# 01-USER_IO.net
KiCad netlist of a schematic drawn in Altium Designer
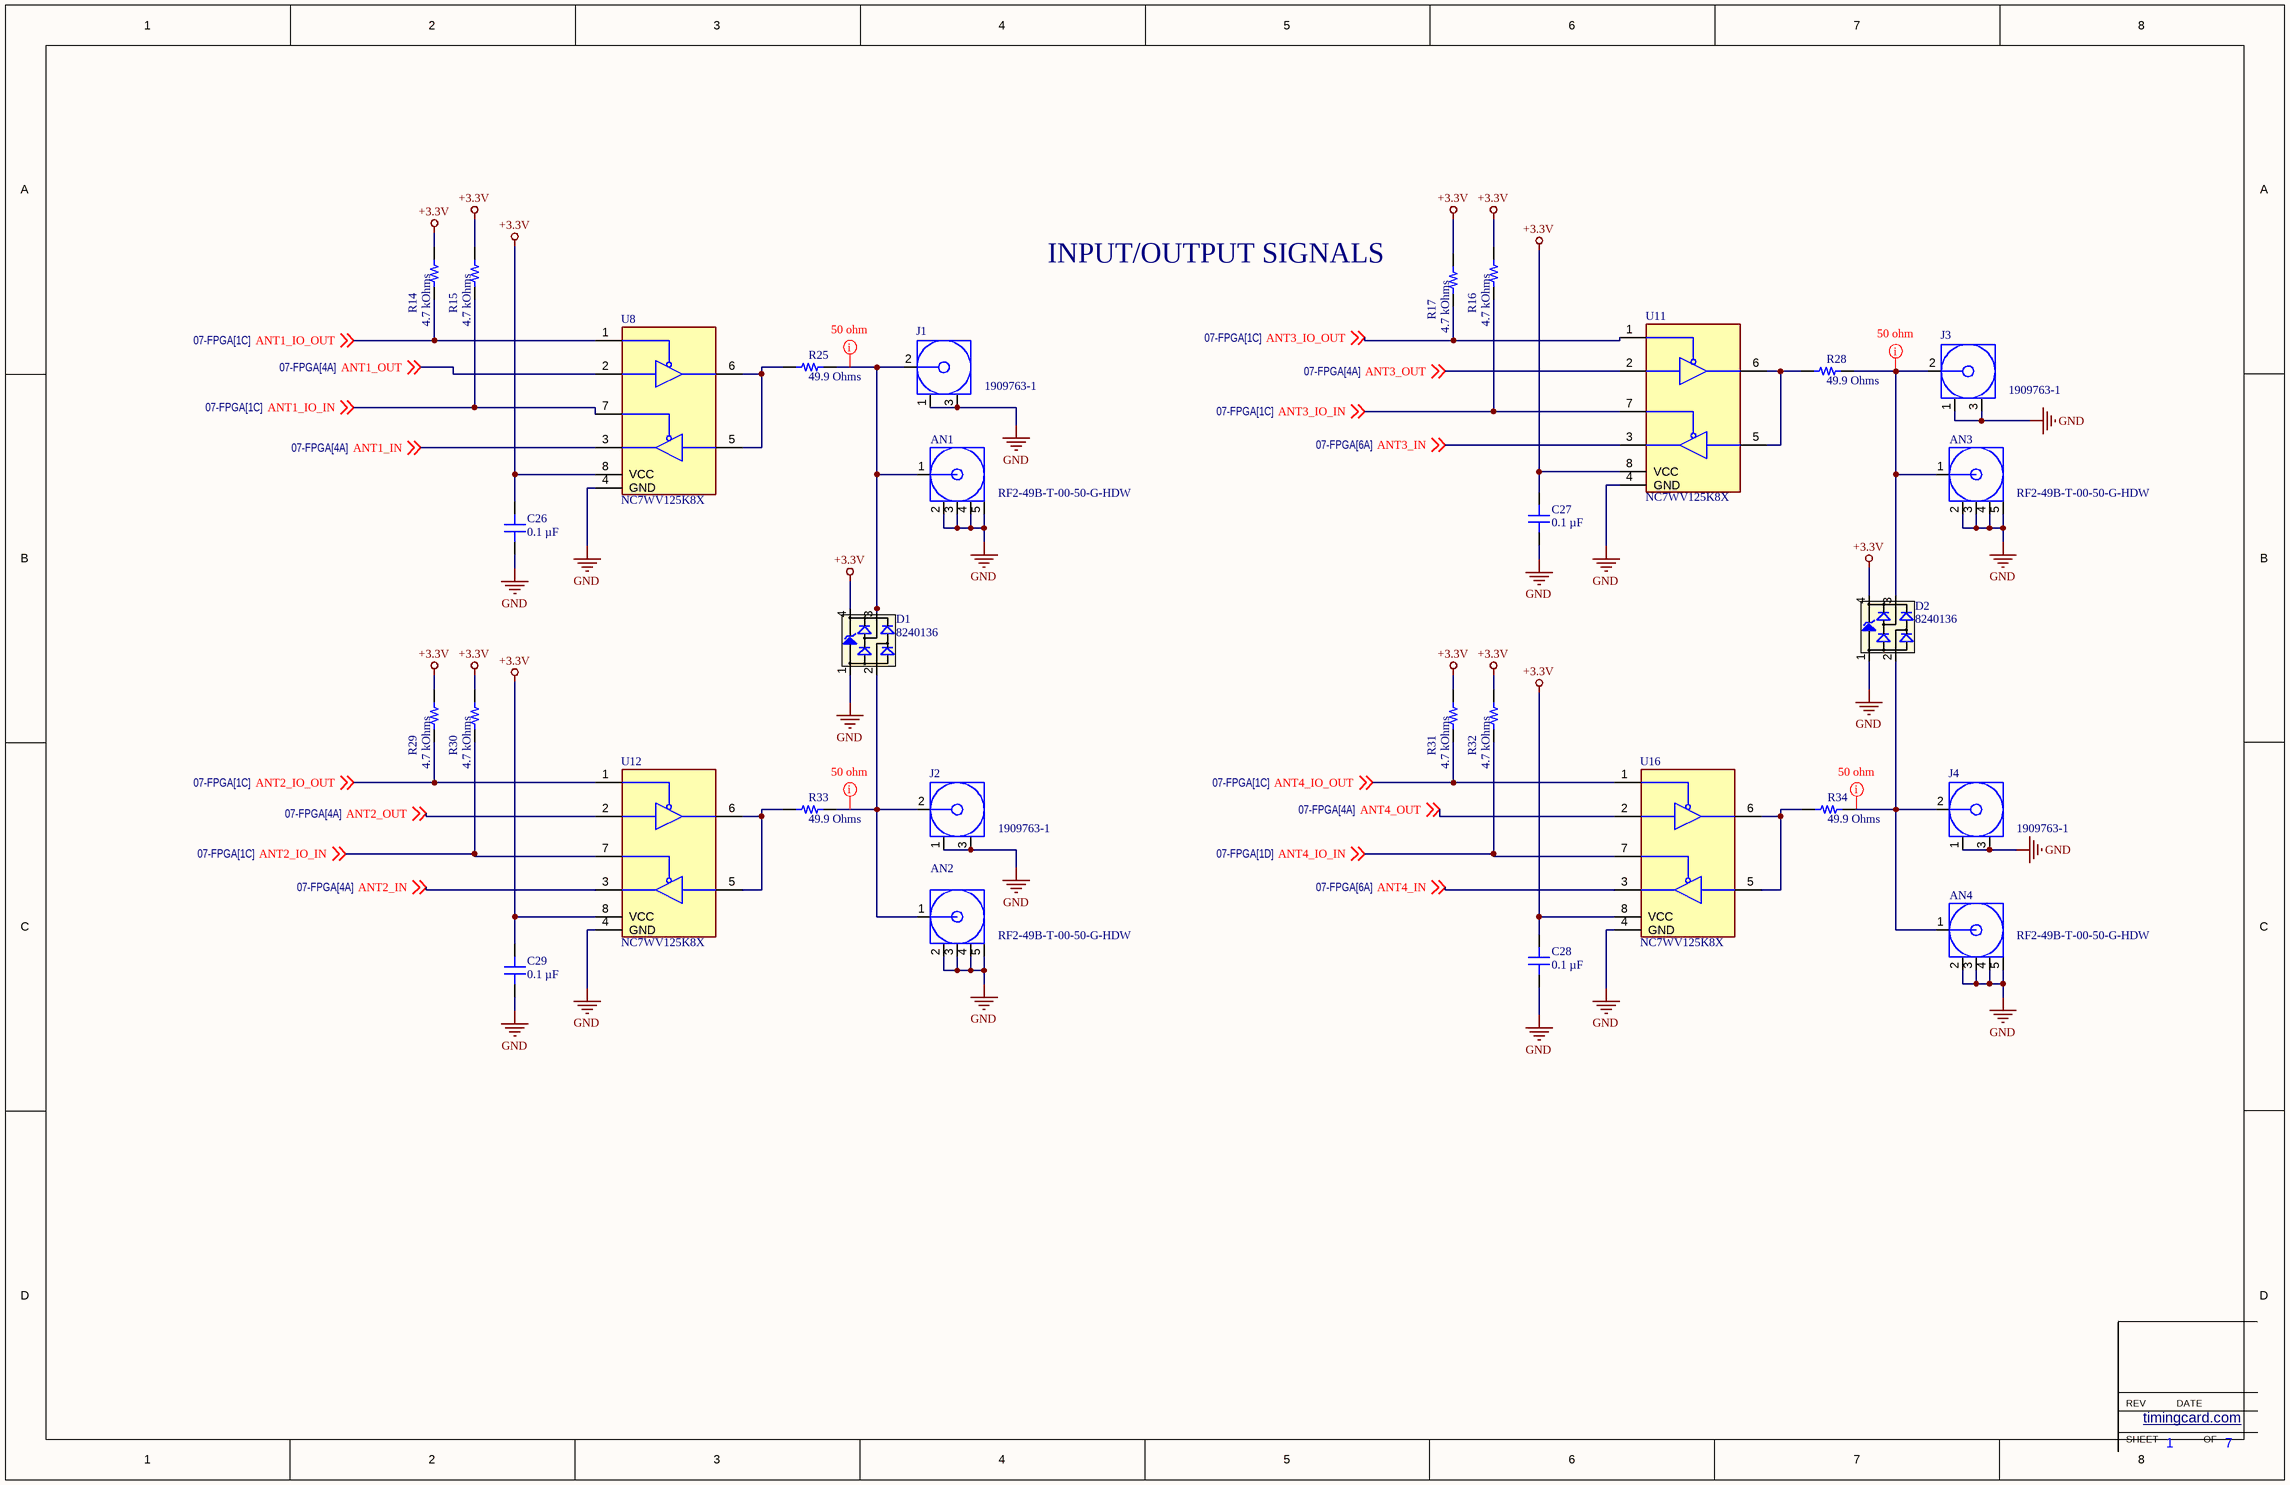
[diagram p0: 01-USER_IO.SchDoc]

(export (version "E")
  (design (tool "Eeschema 10.0.6"))
  (components
    (comp (ref "AN1")
      (value "RF2-49B-T-00-50-G-HDW")
      (footprint "SamacSys:RF249BT0050GHDW")
      (description "Connector")
      (libsource (lib "SamacSys") (part "RF2-49B-T-00-50-G-HDW"))
    )
    (comp (ref "AN2")
      (value "RF2-49B-T-00-50-G-HDW")
      (footprint "SamacSys:RF249BT0050GHDW")
      (description "Connector")
      (libsource (lib "SamacSys") (part "RF2-49B-T-00-50-G-HDW"))
    )
    (comp (ref "AN3")
      (value "RF2-49B-T-00-50-G-HDW")
      (footprint "SamacSys:RF249BT0050GHDW")
      (description "Connector")
      (libsource (lib "SamacSys") (part "RF2-49B-T-00-50-G-HDW"))
    )
    (comp (ref "AN4")
      (value "RF2-49B-T-00-50-G-HDW")
      (footprint "SamacSys:RF249BT0050GHDW")
      (description "Connector")
      (libsource (lib "SamacSys") (part "RF2-49B-T-00-50-G-HDW"))
    )
    (comp (ref "C26")
      (value "0.1 µF")
      (footprint "CAP 0402_1005")
      (description "CAP CER 0.1UF 50V X7R 0402")
      (fields (field (name "TOLERANCE") "±10%") (field (name "PART NUMBER") "CC0402KRX7R9BB104"))
      (libsource (lib "Celestial Altium Library - altium_library") (part "Capacitor"))
    )
    (comp (ref "C27")
      (value "0.1 µF")
      (footprint "CAP 0402_1005")
      (description "CAP CER 0.1UF 50V X7R 0402")
      (fields (field (name "TOLERANCE") "±10%") (field (name "PART NUMBER") "CC0402KRX7R9BB104"))
      (libsource (lib "Celestial Altium Library - altium_library") (part "Capacitor"))
    )
    (comp (ref "C28")
      (value "0.1 µF")
      (footprint "CAP 0402_1005")
      (description "CAP CER 0.1UF 50V X7R 0402")
      (fields (field (name "TOLERANCE") "±10%") (field (name "PART NUMBER") "CC0402KRX7R9BB104"))
      (libsource (lib "Celestial Altium Library - altium_library") (part "Capacitor"))
    )
    (comp (ref "C29")
      (value "0.1 µF")
      (footprint "CAP 0402_1005")
      (description "CAP CER 0.1UF 50V X7R 0402")
      (fields (field (name "TOLERANCE") "±10%") (field (name "PART NUMBER") "CC0402KRX7R9BB104"))
      (libsource (lib "Celestial Altium Library - altium_library") (part "Capacitor"))
    )
    (comp (ref "D1")
      (value "8240136")
      (footprint "SOT143-4L")
      (description "TVS Diode WE-TVS-HS, VRWM=3.3V")
      (fields (field (name "MANUFACTURER") "Wuerth Elektronik"))
      (libsource (lib "Altium Content Vault") (part "WE-TVS-HS-4"))
    )
    (comp (ref "D2")
      (value "8240136")
      (footprint "SOT143-4L")
      (description "TVS Diode WE-TVS-HS, VRWM=3.3V")
      (fields (field (name "MANUFACTURER") "Wuerth Elektronik"))
      (libsource (lib "Altium Content Vault") (part "WE-TVS-HS-4"))
    )
    (comp (ref "J1")
      (value "1909763-1")
      (footprint "TECO-1909763-1_V")
      (description "Ultra Miniature Coaxial Connector Jack, 60 V, 50 Ohm, -40 to 90 degC, RoHS, Tape and Reel")
      (fields (field (name "MANUFACTURER") "TE Connectivity"))
      (libsource (lib "Altium Content Vault") (part "CN-1P-M-RF3"))
    )
    (comp (ref "J2")
      (value "1909763-1")
      (footprint "TECO-1909763-1_V")
      (description "Ultra Miniature Coaxial Connector Jack, 60 V, 50 Ohm, -40 to 90 degC, RoHS, Tape and Reel")
      (fields (field (name "MANUFACTURER") "TE Connectivity"))
      (libsource (lib "Altium Content Vault") (part "CN-1P-M-RF3"))
    )
    (comp (ref "J3")
      (value "1909763-1")
      (footprint "TECO-1909763-1_V")
      (description "Ultra Miniature Coaxial Connector Jack, 60 V, 50 Ohm, -40 to 90 degC, RoHS, Tape and Reel")
      (fields (field (name "MANUFACTURER") "TE Connectivity"))
      (libsource (lib "Altium Content Vault") (part "CN-1P-M-RF3"))
    )
    (comp (ref "J4")
      (value "1909763-1")
      (footprint "TECO-1909763-1_V")
      (description "Ultra Miniature Coaxial Connector Jack, 60 V, 50 Ohm, -40 to 90 degC, RoHS, Tape and Reel")
      (fields (field (name "MANUFACTURER") "TE Connectivity"))
      (libsource (lib "Altium Content Vault") (part "CN-1P-M-RF3"))
    )
    (comp (ref "R14")
      (value "4.7 kOhms")
      (footprint "YAGEO RES 0402_1005")
      (description "RES 4.7K OHM 1% 1/16W 0402")
      (fields (field (name "MANUFACTURER") "Yageo") (field (name "PART NUMBER") "RC0402FR-074K7L"))
      (libsource (lib "Celestial Altium Library - altium_library") (part "Resistor"))
    )
    (comp (ref "R15")
      (value "4.7 kOhms")
      (footprint "YAGEO RES 0402_1005")
      (description "RES 4.7K OHM 1% 1/16W 0402")
      (fields (field (name "MANUFACTURER") "Yageo") (field (name "PART NUMBER") "RC0402FR-074K7L"))
      (libsource (lib "Celestial Altium Library - altium_library") (part "Resistor"))
    )
    (comp (ref "R16")
      (value "4.7 kOhms")
      (footprint "YAGEO RES 0402_1005")
      (description "RES 4.7K OHM 1% 1/16W 0402")
      (fields (field (name "MANUFACTURER") "Yageo") (field (name "PART NUMBER") "RC0402FR-074K7L"))
      (libsource (lib "Celestial Altium Library - altium_library") (part "Resistor"))
    )
    (comp (ref "R17")
      (value "4.7 kOhms")
      (footprint "YAGEO RES 0402_1005")
      (description "RES 4.7K OHM 1% 1/16W 0402")
      (fields (field (name "MANUFACTURER") "Yageo") (field (name "PART NUMBER") "RC0402FR-074K7L"))
      (libsource (lib "Celestial Altium Library - altium_library") (part "Resistor"))
    )
    (comp (ref "R25")
      (value "49.9 Ohms")
      (footprint "YAGEO RES 0402_1005")
      (description "RES 49.9 OHM 1% 1/16W 0402")
      (fields (field (name "PART NUMBER") "RC0402FR-0749R9L") (field (name "MANUFACTURER") "Yageo"))
      (libsource (lib "Celestial Altium Library - altium_library") (part "Resistor"))
    )
    (comp (ref "R28")
      (value "49.9 Ohms")
      (footprint "YAGEO RES 0402_1005")
      (description "RES 49.9 OHM 1% 1/16W 0402")
      (fields (field (name "PART NUMBER") "RC0402FR-0749R9L") (field (name "MANUFACTURER") "Yageo"))
      (libsource (lib "Celestial Altium Library - altium_library") (part "Resistor"))
    )
    (comp (ref "R29")
      (value "4.7 kOhms")
      (footprint "YAGEO RES 0402_1005")
      (description "RES 4.7K OHM 1% 1/16W 0402")
      (fields (field (name "MANUFACTURER") "Yageo") (field (name "PART NUMBER") "RC0402FR-074K7L"))
      (libsource (lib "Celestial Altium Library - altium_library") (part "Resistor"))
    )
    (comp (ref "R30")
      (value "4.7 kOhms")
      (footprint "YAGEO RES 0402_1005")
      (description "RES 4.7K OHM 1% 1/16W 0402")
      (fields (field (name "MANUFACTURER") "Yageo") (field (name "PART NUMBER") "RC0402FR-074K7L"))
      (libsource (lib "Celestial Altium Library - altium_library") (part "Resistor"))
    )
    (comp (ref "R31")
      (value "4.7 kOhms")
      (footprint "YAGEO RES 0402_1005")
      (description "RES 4.7K OHM 1% 1/16W 0402")
      (fields (field (name "MANUFACTURER") "Yageo") (field (name "PART NUMBER") "RC0402FR-074K7L"))
      (libsource (lib "Celestial Altium Library - altium_library") (part "Resistor"))
    )
    (comp (ref "R32")
      (value "4.7 kOhms")
      (footprint "YAGEO RES 0402_1005")
      (description "RES 4.7K OHM 1% 1/16W 0402")
      (fields (field (name "MANUFACTURER") "Yageo") (field (name "PART NUMBER") "RC0402FR-074K7L"))
      (libsource (lib "Celestial Altium Library - altium_library") (part "Resistor"))
    )
    (comp (ref "R33")
      (value "49.9 Ohms")
      (footprint "YAGEO RES 0402_1005")
      (description "RES 49.9 OHM 1% 1/16W 0402")
      (fields (field (name "PART NUMBER") "RC0402FR-0749R9L") (field (name "MANUFACTURER") "Yageo"))
      (libsource (lib "Celestial Altium Library - altium_library") (part "Resistor"))
    )
    (comp (ref "R34")
      (value "49.9 Ohms")
      (footprint "YAGEO RES 0402_1005")
      (description "RES 49.9 OHM 1% 1/16W 0402")
      (fields (field (name "PART NUMBER") "RC0402FR-0749R9L") (field (name "MANUFACTURER") "Yageo"))
      (libsource (lib "Celestial Altium Library - altium_library") (part "Resistor"))
    )
    (comp (ref "U8")
      (value "NC7WV125K8X")
      (footprint "SamacSys:SOP50P310X90-8N")
      (description "Integrated Circuit")
      (fields (field (name "MOUSER PART NUMBER") "512-NC7WV125K8X"))
      (libsource (lib "SamacSys") (part "NC7WV125K8X"))
    )
    (comp (ref "U11")
      (value "NC7WV125K8X")
      (footprint "SamacSys:SOP50P310X90-8N")
      (description "Integrated Circuit")
      (fields (field (name "MOUSER PART NUMBER") "512-NC7WV125K8X"))
      (libsource (lib "SamacSys") (part "NC7WV125K8X"))
    )
    (comp (ref "U12")
      (value "NC7WV125K8X")
      (footprint "SamacSys:SOP50P310X90-8N")
      (description "Integrated Circuit")
      (fields (field (name "MOUSER PART NUMBER") "512-NC7WV125K8X"))
      (libsource (lib "SamacSys") (part "NC7WV125K8X"))
    )
    (comp (ref "U16")
      (value "NC7WV125K8X")
      (footprint "SamacSys:SOP50P310X90-8N")
      (description "Integrated Circuit")
      (fields (field (name "MOUSER PART NUMBER") "512-NC7WV125K8X"))
      (libsource (lib "SamacSys") (part "NC7WV125K8X"))
    )
  )
  (nets
    (net (code "1") (name "+3.3V") (class "Default")
      (node (ref "C26") (pin "1") (pinfunction "1_1") (pintype "passive"))
      (node (ref "C27") (pin "1") (pinfunction "1_1") (pintype "passive"))
      (node (ref "C28") (pin "1") (pinfunction "1_1") (pintype "passive"))
      (node (ref "C29") (pin "1") (pinfunction "1_1") (pintype "passive"))
      (node (ref "D1") (pin "4") (pinfunction "VDD_4") (pintype "passive"))
      (node (ref "D2") (pin "4") (pinfunction "VDD_4") (pintype "passive"))
      (node (ref "R14") (pin "1") (pinfunction "1_1") (pintype "passive"))
      (node (ref "R15") (pin "1") (pinfunction "1_1") (pintype "passive"))
      (node (ref "R16") (pin "1") (pinfunction "1_1") (pintype "passive"))
      (node (ref "R17") (pin "1") (pinfunction "1_1") (pintype "passive"))
      (node (ref "R29") (pin "1") (pinfunction "1_1") (pintype "passive"))
      (node (ref "R30") (pin "1") (pinfunction "1_1") (pintype "passive"))
      (node (ref "R31") (pin "1") (pinfunction "1_1") (pintype "passive"))
      (node (ref "R32") (pin "1") (pinfunction "1_1") (pintype "passive"))
      (node (ref "U11") (pin "8") (pinfunction "VCC_8") (pintype "passive"))
      (node (ref "U12") (pin "8") (pinfunction "VCC_8") (pintype "passive"))
      (node (ref "U16") (pin "8") (pinfunction "VCC_8") (pintype "passive"))
      (node (ref "U8") (pin "8") (pinfunction "VCC_8") (pintype "passive"))
    )
    (net (code "2") (name "ANT1_IN") (class "Default") (node (ref "U8") (pin "3") (pintype "passive")))
    (net (code "3") (name "ANT1_IO_IN") (class "Default")
      (node (ref "R15") (pin "2") (pinfunction "2_2") (pintype "passive"))
      (node (ref "U8") (pin "7") (pintype "passive"))
    )
    (net (code "4") (name "ANT1_IO_OUT") (class "Default")
      (node (ref "R14") (pin "2") (pinfunction "2_2") (pintype "passive"))
      (node (ref "U8") (pin "1") (pintype "passive"))
    )
    (net (code "5") (name "ANT1_OUT") (class "Default") (node (ref "U8") (pin "2") (pintype "passive")))
    (net (code "6") (name "ANT2_IN") (class "Default") (node (ref "U12") (pin "3") (pintype "passive")))
    (net (code "7") (name "ANT2_IO_IN") (class "Default")
      (node (ref "R30") (pin "2") (pinfunction "2_2") (pintype "passive"))
      (node (ref "U12") (pin "7") (pintype "passive"))
    )
    (net (code "8") (name "ANT2_IO_OUT") (class "Default")
      (node (ref "R29") (pin "2") (pinfunction "2_2") (pintype "passive"))
      (node (ref "U12") (pin "1") (pintype "passive"))
    )
    (net (code "9") (name "ANT2_OUT") (class "Default") (node (ref "U12") (pin "2") (pintype "passive")))
    (net (code "10") (name "ANT3_IN") (class "Default") (node (ref "U11") (pin "3") (pintype "passive")))
    (net (code "11") (name "ANT3_IO_IN") (class "Default")
      (node (ref "R16") (pin "2") (pinfunction "2_2") (pintype "passive"))
      (node (ref "U11") (pin "7") (pintype "passive"))
    )
    (net (code "12") (name "ANT3_IO_OUT") (class "Default")
      (node (ref "R17") (pin "2") (pinfunction "2_2") (pintype "passive"))
      (node (ref "U11") (pin "1") (pintype "passive"))
    )
    (net (code "13") (name "ANT3_OUT") (class "Default") (node (ref "U11") (pin "2") (pintype "passive")))
    (net (code "14") (name "ANT4_IN") (class "Default") (node (ref "U16") (pin "3") (pintype "passive")))
    (net (code "15") (name "ANT4_IO_IN") (class "Default")
      (node (ref "R32") (pin "2") (pinfunction "2_2") (pintype "passive"))
      (node (ref "U16") (pin "7") (pintype "passive"))
    )
    (net (code "16") (name "ANT4_IO_OUT") (class "Default")
      (node (ref "R31") (pin "2") (pinfunction "2_2") (pintype "passive"))
      (node (ref "U16") (pin "1") (pintype "passive"))
    )
    (net (code "17") (name "ANT4_OUT") (class "Default") (node (ref "U16") (pin "2") (pintype "passive")))
    (net (code "18") (name "GND") (class "Default")
      (node (ref "AN1") (pin "2") (pinfunction "2_2") (pintype "passive"))
      (node (ref "AN1") (pin "3") (pinfunction "3_3") (pintype "passive"))
      (node (ref "AN1") (pin "4") (pinfunction "4_4") (pintype "passive"))
      (node (ref "AN1") (pin "5") (pinfunction "5_5") (pintype "passive"))
      (node (ref "AN2") (pin "2") (pinfunction "2_2") (pintype "passive"))
      (node (ref "AN2") (pin "3") (pinfunction "3_3") (pintype "passive"))
      (node (ref "AN2") (pin "4") (pinfunction "4_4") (pintype "passive"))
      (node (ref "AN2") (pin "5") (pinfunction "5_5") (pintype "passive"))
      (node (ref "AN3") (pin "2") (pinfunction "2_2") (pintype "passive"))
      (node (ref "AN3") (pin "3") (pinfunction "3_3") (pintype "passive"))
      (node (ref "AN3") (pin "4") (pinfunction "4_4") (pintype "passive"))
      (node (ref "AN3") (pin "5") (pinfunction "5_5") (pintype "passive"))
      (node (ref "AN4") (pin "2") (pinfunction "2_2") (pintype "passive"))
      (node (ref "AN4") (pin "3") (pinfunction "3_3") (pintype "passive"))
      (node (ref "AN4") (pin "4") (pinfunction "4_4") (pintype "passive"))
      (node (ref "AN4") (pin "5") (pinfunction "5_5") (pintype "passive"))
      (node (ref "C26") (pin "2") (pinfunction "2_2") (pintype "passive"))
      (node (ref "C27") (pin "2") (pinfunction "2_2") (pintype "passive"))
      (node (ref "C28") (pin "2") (pinfunction "2_2") (pintype "passive"))
      (node (ref "C29") (pin "2") (pinfunction "2_2") (pintype "passive"))
      (node (ref "D1") (pin "1") (pinfunction "GND_1") (pintype "passive"))
      (node (ref "D2") (pin "1") (pinfunction "GND_1") (pintype "passive"))
      (node (ref "J1") (pin "1") (pinfunction "1_1") (pintype "passive"))
      (node (ref "J1") (pin "3") (pinfunction "3_3") (pintype "passive"))
      (node (ref "J2") (pin "1") (pinfunction "1_1") (pintype "passive"))
      (node (ref "J2") (pin "3") (pinfunction "3_3") (pintype "passive"))
      (node (ref "J3") (pin "1") (pinfunction "1_1") (pintype "passive"))
      (node (ref "J3") (pin "3") (pinfunction "3_3") (pintype "passive"))
      (node (ref "J4") (pin "1") (pinfunction "1_1") (pintype "passive"))
      (node (ref "J4") (pin "3") (pinfunction "3_3") (pintype "passive"))
      (node (ref "U11") (pin "4") (pinfunction "GND_4") (pintype "passive"))
      (node (ref "U12") (pin "4") (pinfunction "GND_4") (pintype "passive"))
      (node (ref "U16") (pin "4") (pinfunction "GND_4") (pintype "passive"))
      (node (ref "U8") (pin "4") (pinfunction "GND_4") (pintype "passive"))
    )
    (net (code "19") (name "Net-(D1-I{slash}O1)") (class "Default")
      (node (ref "AN2") (pin "1") (pinfunction "1_1") (pintype "passive"))
      (node (ref "D1") (pin "2") (pinfunction "I/O1_2") (pintype "passive"))
      (node (ref "J2") (pin "2") (pinfunction "2_2") (pintype "passive"))
      (node (ref "R33") (pin "2") (pinfunction "2_2") (pintype "passive"))
    )
    (net (code "20") (name "Net-(D1-I{slash}O2)") (class "Default")
      (node (ref "AN1") (pin "1") (pinfunction "1_1") (pintype "passive"))
      (node (ref "D1") (pin "3") (pinfunction "I/O2_3") (pintype "passive"))
      (node (ref "J1") (pin "2") (pinfunction "2_2") (pintype "passive"))
      (node (ref "R25") (pin "2") (pinfunction "2_2") (pintype "passive"))
    )
    (net (code "21") (name "Net-(D2-I{slash}O1)") (class "Default")
      (node (ref "AN4") (pin "1") (pinfunction "1_1") (pintype "passive"))
      (node (ref "D2") (pin "2") (pinfunction "I/O1_2") (pintype "passive"))
      (node (ref "J4") (pin "2") (pinfunction "2_2") (pintype "passive"))
      (node (ref "R34") (pin "2") (pinfunction "2_2") (pintype "passive"))
    )
    (net (code "22") (name "Net-(D2-I{slash}O2)") (class "Default")
      (node (ref "AN3") (pin "1") (pinfunction "1_1") (pintype "passive"))
      (node (ref "D2") (pin "3") (pinfunction "I/O2_3") (pintype "passive"))
      (node (ref "J3") (pin "2") (pinfunction "2_2") (pintype "passive"))
      (node (ref "R28") (pin "2") (pinfunction "2_2") (pintype "passive"))
    )
    (net (code "23") (name "Net-(R25-Pad1)") (class "Default")
      (node (ref "R25") (pin "1") (pinfunction "1_1") (pintype "passive"))
      (node (ref "U8") (pin "5") (pintype "passive"))
      (node (ref "U8") (pin "6") (pintype "passive"))
    )
    (net (code "24") (name "Net-(R28-Pad1)") (class "Default")
      (node (ref "R28") (pin "1") (pinfunction "1_1") (pintype "passive"))
      (node (ref "U11") (pin "5") (pintype "passive"))
      (node (ref "U11") (pin "6") (pintype "passive"))
    )
    (net (code "25") (name "Net-(R33-Pad1)") (class "Default")
      (node (ref "R33") (pin "1") (pinfunction "1_1") (pintype "passive"))
      (node (ref "U12") (pin "5") (pintype "passive"))
      (node (ref "U12") (pin "6") (pintype "passive"))
    )
    (net (code "26") (name "Net-(R34-Pad1)") (class "Default")
      (node (ref "R34") (pin "1") (pinfunction "1_1") (pintype "passive"))
      (node (ref "U16") (pin "5") (pintype "passive"))
      (node (ref "U16") (pin "6") (pintype "passive"))
    )
  )
)
